# expansion.net
KiCad netlist of a schematic drawn in EAGLE
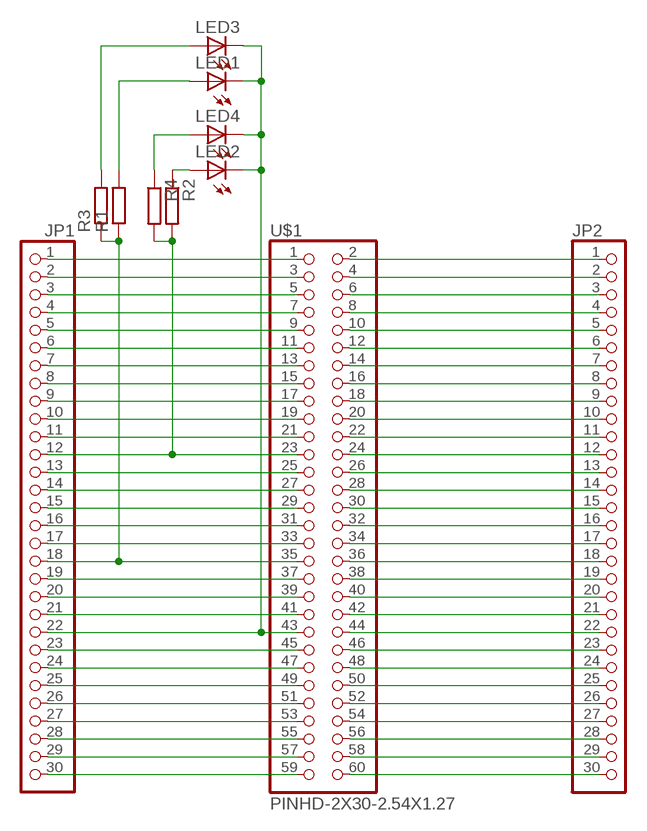
[diagram p0: schematic, sheet 1]

(export (version "E")
  (design (tool "Eeschema 10.0.6"))
  (components
    (comp (ref "JP1")
      (value "PINHD-1X30")
      (footprint "eagle-import:1X30")
      (libsource (lib "eagle-import") (part "PINHD-1X30"))
    )
    (comp (ref "JP2")
      (value "PINHD-1X30")
      (footprint "eagle-import:1X30")
      (libsource (lib "eagle-import") (part "PINHD-1X30"))
    )
    (comp (ref "LED1")
      (value "LEDCHIP-LED0805")
      (footprint "eagle-import:CHIP-LED0805")
      (libsource (lib "eagle-import") (part "LEDCHIP-LED0805"))
    )
    (comp (ref "LED2")
      (value "LEDCHIP-LED0805")
      (footprint "eagle-import:CHIP-LED0805")
      (libsource (lib "eagle-import") (part "LEDCHIP-LED0805"))
    )
    (comp (ref "LED3")
      (value "LEDCHIP-LED0805")
      (footprint "eagle-import:CHIP-LED0805")
      (libsource (lib "eagle-import") (part "LEDCHIP-LED0805"))
    )
    (comp (ref "LED4")
      (value "LEDCHIP-LED0805")
      (footprint "eagle-import:CHIP-LED0805")
      (libsource (lib "eagle-import") (part "LEDCHIP-LED0805"))
    )
    (comp (ref "R1")
      (value "R-EU_R0805")
      (footprint "eagle-import:R0805")
      (libsource (lib "eagle-import") (part "R-EU_R0805"))
    )
    (comp (ref "R2")
      (value "R-EU_R0805")
      (footprint "eagle-import:R0805")
      (libsource (lib "eagle-import") (part "R-EU_R0805"))
    )
    (comp (ref "R3")
      (value "R-EU_R0805")
      (footprint "eagle-import:R0805")
      (libsource (lib "eagle-import") (part "R-EU_R0805"))
    )
    (comp (ref "R4")
      (value "R-EU_R0805")
      (footprint "eagle-import:R0805")
      (libsource (lib "eagle-import") (part "R-EU_R0805"))
    )
    (comp (ref "U$1")
      (value "PINHD-2X30-2.54X1.27")
      (footprint "eagle-import:PINHD-2X30-2.54X1.27")
      (libsource (lib "eagle-import") (part "PINHD-2X30-2.54X1.27"))
    )
  )
  (nets
    (net (code "1") (name "Net-(JP1-Pad1)") (class "Default")
      (node (ref "JP1") (pin "1") (pinfunction "1_1") (pintype "passive"))
      (node (ref "U$1") (pin "1") (pinfunction "1_1") (pintype "passive"))
    )
    (net (code "2") (name "Net-(JP1-Pad2)") (class "Default")
      (node (ref "JP1") (pin "2") (pinfunction "2_2") (pintype "passive"))
      (node (ref "U$1") (pin "3") (pinfunction "3_3") (pintype "passive"))
    )
    (net (code "3") (name "Net-(JP1-Pad3)") (class "Default")
      (node (ref "JP1") (pin "3") (pinfunction "3_3") (pintype "passive"))
      (node (ref "U$1") (pin "5") (pinfunction "5_5") (pintype "passive"))
    )
    (net (code "4") (name "Net-(JP1-Pad4)") (class "Default")
      (node (ref "JP1") (pin "4") (pinfunction "4_4") (pintype "passive"))
      (node (ref "U$1") (pin "7") (pinfunction "7_7") (pintype "passive"))
    )
    (net (code "5") (name "Net-(JP1-Pad5)") (class "Default")
      (node (ref "JP1") (pin "5") (pinfunction "5_5") (pintype "passive"))
      (node (ref "U$1") (pin "9") (pinfunction "9_9") (pintype "passive"))
    )
    (net (code "6") (name "Net-(JP1-Pad6)") (class "Default")
      (node (ref "JP1") (pin "6") (pinfunction "6_6") (pintype "passive"))
      (node (ref "U$1") (pin "11") (pinfunction "11_11") (pintype "passive"))
    )
    (net (code "7") (name "Net-(JP1-Pad7)") (class "Default")
      (node (ref "JP1") (pin "7") (pinfunction "7_7") (pintype "passive"))
      (node (ref "U$1") (pin "13") (pinfunction "13_13") (pintype "passive"))
    )
    (net (code "8") (name "Net-(JP1-Pad8)") (class "Default")
      (node (ref "JP1") (pin "8") (pinfunction "8_8") (pintype "passive"))
      (node (ref "U$1") (pin "15") (pinfunction "15_15") (pintype "passive"))
    )
    (net (code "9") (name "Net-(JP1-Pad9)") (class "Default")
      (node (ref "JP1") (pin "9") (pinfunction "9_9") (pintype "passive"))
      (node (ref "U$1") (pin "17") (pinfunction "17_17") (pintype "passive"))
    )
    (net (code "10") (name "Net-(JP1-Pad10)") (class "Default")
      (node (ref "JP1") (pin "10") (pinfunction "10_10") (pintype "passive"))
      (node (ref "U$1") (pin "19") (pinfunction "19_19") (pintype "passive"))
    )
    (net (code "11") (name "Net-(JP1-Pad11)") (class "Default")
      (node (ref "JP1") (pin "11") (pinfunction "11_11") (pintype "passive"))
      (node (ref "U$1") (pin "21") (pinfunction "21_21") (pintype "passive"))
    )
    (net (code "12") (name "Net-(JP1-Pad12)") (class "Default")
      (node (ref "JP1") (pin "12") (pinfunction "12_12") (pintype "passive"))
      (node (ref "R2") (pin "2") (pinfunction "2_2") (pintype "passive"))
      (node (ref "R4") (pin "2") (pinfunction "2_2") (pintype "passive"))
      (node (ref "U$1") (pin "23") (pinfunction "23_23") (pintype "passive"))
    )
    (net (code "13") (name "Net-(JP1-Pad13)") (class "Default")
      (node (ref "JP1") (pin "13") (pinfunction "13_13") (pintype "passive"))
      (node (ref "U$1") (pin "25") (pinfunction "25_25") (pintype "passive"))
    )
    (net (code "14") (name "Net-(JP1-Pad14)") (class "Default")
      (node (ref "JP1") (pin "14") (pinfunction "14_14") (pintype "passive"))
      (node (ref "U$1") (pin "27") (pinfunction "27_27") (pintype "passive"))
    )
    (net (code "15") (name "Net-(JP1-Pad15)") (class "Default")
      (node (ref "JP1") (pin "15") (pinfunction "15_15") (pintype "passive"))
      (node (ref "U$1") (pin "29") (pinfunction "29_29") (pintype "passive"))
    )
    (net (code "16") (name "Net-(JP1-Pad16)") (class "Default")
      (node (ref "JP1") (pin "16") (pinfunction "16_16") (pintype "passive"))
      (node (ref "U$1") (pin "31") (pinfunction "31_31") (pintype "passive"))
    )
    (net (code "17") (name "Net-(JP1-Pad17)") (class "Default")
      (node (ref "JP1") (pin "17") (pinfunction "17_17") (pintype "passive"))
      (node (ref "U$1") (pin "33") (pinfunction "33_33") (pintype "passive"))
    )
    (net (code "18") (name "Net-(JP1-Pad18)") (class "Default")
      (node (ref "JP1") (pin "18") (pinfunction "18_18") (pintype "passive"))
      (node (ref "R1") (pin "1") (pinfunction "1_1") (pintype "passive"))
      (node (ref "R3") (pin "1") (pinfunction "1_1") (pintype "passive"))
      (node (ref "U$1") (pin "35") (pinfunction "35_35") (pintype "passive"))
    )
    (net (code "19") (name "Net-(JP1-Pad19)") (class "Default")
      (node (ref "JP1") (pin "19") (pinfunction "19_19") (pintype "passive"))
      (node (ref "U$1") (pin "37") (pinfunction "37_37") (pintype "passive"))
    )
    (net (code "20") (name "Net-(JP1-Pad20)") (class "Default")
      (node (ref "JP1") (pin "20") (pinfunction "20_20") (pintype "passive"))
      (node (ref "U$1") (pin "39") (pinfunction "39_39") (pintype "passive"))
    )
    (net (code "21") (name "Net-(JP1-Pad21)") (class "Default")
      (node (ref "JP1") (pin "21") (pinfunction "21_21") (pintype "passive"))
      (node (ref "U$1") (pin "41") (pinfunction "41_41") (pintype "passive"))
    )
    (net (code "22") (name "Net-(JP1-Pad22)") (class "Default")
      (node (ref "JP1") (pin "22") (pinfunction "22_22") (pintype "passive"))
      (node (ref "LED1") (pin "C") (pinfunction "C_C") (pintype "passive"))
      (node (ref "LED2") (pin "C") (pinfunction "C_C") (pintype "passive"))
      (node (ref "LED3") (pin "C") (pinfunction "C_C") (pintype "passive"))
      (node (ref "LED4") (pin "C") (pinfunction "C_C") (pintype "passive"))
      (node (ref "U$1") (pin "43") (pinfunction "43_43") (pintype "passive"))
    )
    (net (code "23") (name "Net-(JP1-Pad23)") (class "Default")
      (node (ref "JP1") (pin "23") (pinfunction "23_23") (pintype "passive"))
      (node (ref "U$1") (pin "45") (pinfunction "45_45") (pintype "passive"))
    )
    (net (code "24") (name "Net-(JP1-Pad24)") (class "Default")
      (node (ref "JP1") (pin "24") (pinfunction "24_24") (pintype "passive"))
      (node (ref "U$1") (pin "47") (pinfunction "47_47") (pintype "passive"))
    )
    (net (code "25") (name "Net-(JP1-Pad25)") (class "Default")
      (node (ref "JP1") (pin "25") (pinfunction "25_25") (pintype "passive"))
      (node (ref "U$1") (pin "49") (pinfunction "49_49") (pintype "passive"))
    )
    (net (code "26") (name "Net-(JP1-Pad26)") (class "Default")
      (node (ref "JP1") (pin "26") (pinfunction "26_26") (pintype "passive"))
      (node (ref "U$1") (pin "51") (pinfunction "51_51") (pintype "passive"))
    )
    (net (code "27") (name "Net-(JP1-Pad27)") (class "Default")
      (node (ref "JP1") (pin "27") (pinfunction "27_27") (pintype "passive"))
      (node (ref "U$1") (pin "53") (pinfunction "53_53") (pintype "passive"))
    )
    (net (code "28") (name "Net-(JP1-Pad28)") (class "Default")
      (node (ref "JP1") (pin "28") (pinfunction "28_28") (pintype "passive"))
      (node (ref "U$1") (pin "55") (pinfunction "55_55") (pintype "passive"))
    )
    (net (code "29") (name "Net-(JP1-Pad29)") (class "Default")
      (node (ref "JP1") (pin "29") (pinfunction "29_29") (pintype "passive"))
      (node (ref "U$1") (pin "57") (pinfunction "57_57") (pintype "passive"))
    )
    (net (code "30") (name "Net-(JP1-Pad30)") (class "Default")
      (node (ref "JP1") (pin "30") (pinfunction "30_30") (pintype "passive"))
      (node (ref "U$1") (pin "59") (pinfunction "59_59") (pintype "passive"))
    )
    (net (code "31") (name "Net-(JP2-Pad1)") (class "Default")
      (node (ref "JP2") (pin "1") (pinfunction "1_1") (pintype "passive"))
      (node (ref "U$1") (pin "2") (pinfunction "2_2") (pintype "passive"))
    )
    (net (code "32") (name "Net-(JP2-Pad2)") (class "Default")
      (node (ref "JP2") (pin "2") (pinfunction "2_2") (pintype "passive"))
      (node (ref "U$1") (pin "4") (pinfunction "4_4") (pintype "passive"))
    )
    (net (code "33") (name "Net-(JP2-Pad3)") (class "Default")
      (node (ref "JP2") (pin "3") (pinfunction "3_3") (pintype "passive"))
      (node (ref "U$1") (pin "6") (pinfunction "6_6") (pintype "passive"))
    )
    (net (code "34") (name "Net-(JP2-Pad4)") (class "Default")
      (node (ref "JP2") (pin "4") (pinfunction "4_4") (pintype "passive"))
      (node (ref "U$1") (pin "8") (pinfunction "8_8") (pintype "passive"))
    )
    (net (code "35") (name "Net-(JP2-Pad5)") (class "Default")
      (node (ref "JP2") (pin "5") (pinfunction "5_5") (pintype "passive"))
      (node (ref "U$1") (pin "10") (pinfunction "10_10") (pintype "passive"))
    )
    (net (code "36") (name "Net-(JP2-Pad6)") (class "Default")
      (node (ref "JP2") (pin "6") (pinfunction "6_6") (pintype "passive"))
      (node (ref "U$1") (pin "12") (pinfunction "12_12") (pintype "passive"))
    )
    (net (code "37") (name "Net-(JP2-Pad7)") (class "Default")
      (node (ref "JP2") (pin "7") (pinfunction "7_7") (pintype "passive"))
      (node (ref "U$1") (pin "14") (pinfunction "14_14") (pintype "passive"))
    )
    (net (code "38") (name "Net-(JP2-Pad8)") (class "Default")
      (node (ref "JP2") (pin "8") (pinfunction "8_8") (pintype "passive"))
      (node (ref "U$1") (pin "16") (pinfunction "16_16") (pintype "passive"))
    )
    (net (code "39") (name "Net-(JP2-Pad9)") (class "Default")
      (node (ref "JP2") (pin "9") (pinfunction "9_9") (pintype "passive"))
      (node (ref "U$1") (pin "18") (pinfunction "18_18") (pintype "passive"))
    )
    (net (code "40") (name "Net-(JP2-Pad10)") (class "Default")
      (node (ref "JP2") (pin "10") (pinfunction "10_10") (pintype "passive"))
      (node (ref "U$1") (pin "20") (pinfunction "20_20") (pintype "passive"))
    )
    (net (code "41") (name "Net-(JP2-Pad11)") (class "Default")
      (node (ref "JP2") (pin "11") (pinfunction "11_11") (pintype "passive"))
      (node (ref "U$1") (pin "22") (pinfunction "22_22") (pintype "passive"))
    )
    (net (code "42") (name "Net-(JP2-Pad12)") (class "Default")
      (node (ref "JP2") (pin "12") (pinfunction "12_12") (pintype "passive"))
      (node (ref "U$1") (pin "24") (pinfunction "24_24") (pintype "passive"))
    )
    (net (code "43") (name "Net-(JP2-Pad13)") (class "Default")
      (node (ref "JP2") (pin "13") (pinfunction "13_13") (pintype "passive"))
      (node (ref "U$1") (pin "26") (pinfunction "26_26") (pintype "passive"))
    )
    (net (code "44") (name "Net-(JP2-Pad14)") (class "Default")
      (node (ref "JP2") (pin "14") (pinfunction "14_14") (pintype "passive"))
      (node (ref "U$1") (pin "28") (pinfunction "28_28") (pintype "passive"))
    )
    (net (code "45") (name "Net-(JP2-Pad15)") (class "Default")
      (node (ref "JP2") (pin "15") (pinfunction "15_15") (pintype "passive"))
      (node (ref "U$1") (pin "30") (pinfunction "30_30") (pintype "passive"))
    )
    (net (code "46") (name "Net-(JP2-Pad16)") (class "Default")
      (node (ref "JP2") (pin "16") (pinfunction "16_16") (pintype "passive"))
      (node (ref "U$1") (pin "32") (pinfunction "32_32") (pintype "passive"))
    )
    (net (code "47") (name "Net-(JP2-Pad17)") (class "Default")
      (node (ref "JP2") (pin "17") (pinfunction "17_17") (pintype "passive"))
      (node (ref "U$1") (pin "34") (pinfunction "34_34") (pintype "passive"))
    )
    (net (code "48") (name "Net-(JP2-Pad18)") (class "Default")
      (node (ref "JP2") (pin "18") (pinfunction "18_18") (pintype "passive"))
      (node (ref "U$1") (pin "36") (pinfunction "36_36") (pintype "passive"))
    )
    (net (code "49") (name "Net-(JP2-Pad19)") (class "Default")
      (node (ref "JP2") (pin "19") (pinfunction "19_19") (pintype "passive"))
      (node (ref "U$1") (pin "38") (pinfunction "38_38") (pintype "passive"))
    )
    (net (code "50") (name "Net-(JP2-Pad20)") (class "Default")
      (node (ref "JP2") (pin "20") (pinfunction "20_20") (pintype "passive"))
      (node (ref "U$1") (pin "40") (pinfunction "40_40") (pintype "passive"))
    )
    (net (code "51") (name "Net-(JP2-Pad21)") (class "Default")
      (node (ref "JP2") (pin "21") (pinfunction "21_21") (pintype "passive"))
      (node (ref "U$1") (pin "42") (pinfunction "42_42") (pintype "passive"))
    )
    (net (code "52") (name "Net-(JP2-Pad22)") (class "Default")
      (node (ref "JP2") (pin "22") (pinfunction "22_22") (pintype "passive"))
      (node (ref "U$1") (pin "44") (pinfunction "44_44") (pintype "passive"))
    )
    (net (code "53") (name "Net-(JP2-Pad23)") (class "Default")
      (node (ref "JP2") (pin "23") (pinfunction "23_23") (pintype "passive"))
      (node (ref "U$1") (pin "46") (pinfunction "46_46") (pintype "passive"))
    )
    (net (code "54") (name "Net-(JP2-Pad24)") (class "Default")
      (node (ref "JP2") (pin "24") (pinfunction "24_24") (pintype "passive"))
      (node (ref "U$1") (pin "48") (pinfunction "48_48") (pintype "passive"))
    )
    (net (code "55") (name "Net-(JP2-Pad25)") (class "Default")
      (node (ref "JP2") (pin "25") (pinfunction "25_25") (pintype "passive"))
      (node (ref "U$1") (pin "50") (pinfunction "50_50") (pintype "passive"))
    )
    (net (code "56") (name "Net-(JP2-Pad26)") (class "Default")
      (node (ref "JP2") (pin "26") (pinfunction "26_26") (pintype "passive"))
      (node (ref "U$1") (pin "52") (pinfunction "52_52") (pintype "passive"))
    )
    (net (code "57") (name "Net-(JP2-Pad27)") (class "Default")
      (node (ref "JP2") (pin "27") (pinfunction "27_27") (pintype "passive"))
      (node (ref "U$1") (pin "54") (pinfunction "54_54") (pintype "passive"))
    )
    (net (code "58") (name "Net-(JP2-Pad28)") (class "Default")
      (node (ref "JP2") (pin "28") (pinfunction "28_28") (pintype "passive"))
      (node (ref "U$1") (pin "56") (pinfunction "56_56") (pintype "passive"))
    )
    (net (code "59") (name "Net-(JP2-Pad29)") (class "Default")
      (node (ref "JP2") (pin "29") (pinfunction "29_29") (pintype "passive"))
      (node (ref "U$1") (pin "58") (pinfunction "58_58") (pintype "passive"))
    )
    (net (code "60") (name "Net-(JP2-Pad30)") (class "Default")
      (node (ref "JP2") (pin "30") (pinfunction "30_30") (pintype "passive"))
      (node (ref "U$1") (pin "60") (pinfunction "60_60") (pintype "passive"))
    )
    (net (code "61") (name "Net-(LED1-PadA)") (class "Default")
      (node (ref "LED1") (pin "A") (pinfunction "A_A") (pintype "passive"))
      (node (ref "R1") (pin "2") (pinfunction "2_2") (pintype "passive"))
    )
    (net (code "62") (name "Net-(LED2-PadA)") (class "Default")
      (node (ref "LED2") (pin "A") (pinfunction "A_A") (pintype "passive"))
      (node (ref "R2") (pin "1") (pinfunction "1_1") (pintype "passive"))
    )
    (net (code "63") (name "Net-(LED3-PadA)") (class "Default")
      (node (ref "LED3") (pin "A") (pinfunction "A_A") (pintype "passive"))
      (node (ref "R3") (pin "2") (pinfunction "2_2") (pintype "passive"))
    )
    (net (code "64") (name "Net-(LED4-PadA)") (class "Default")
      (node (ref "LED4") (pin "A") (pinfunction "A_A") (pintype "passive"))
      (node (ref "R4") (pin "1") (pinfunction "1_1") (pintype "passive"))
    )
  )
)
